# RH039_2.net
KiCad netlist of a schematic drawn in EAGLE
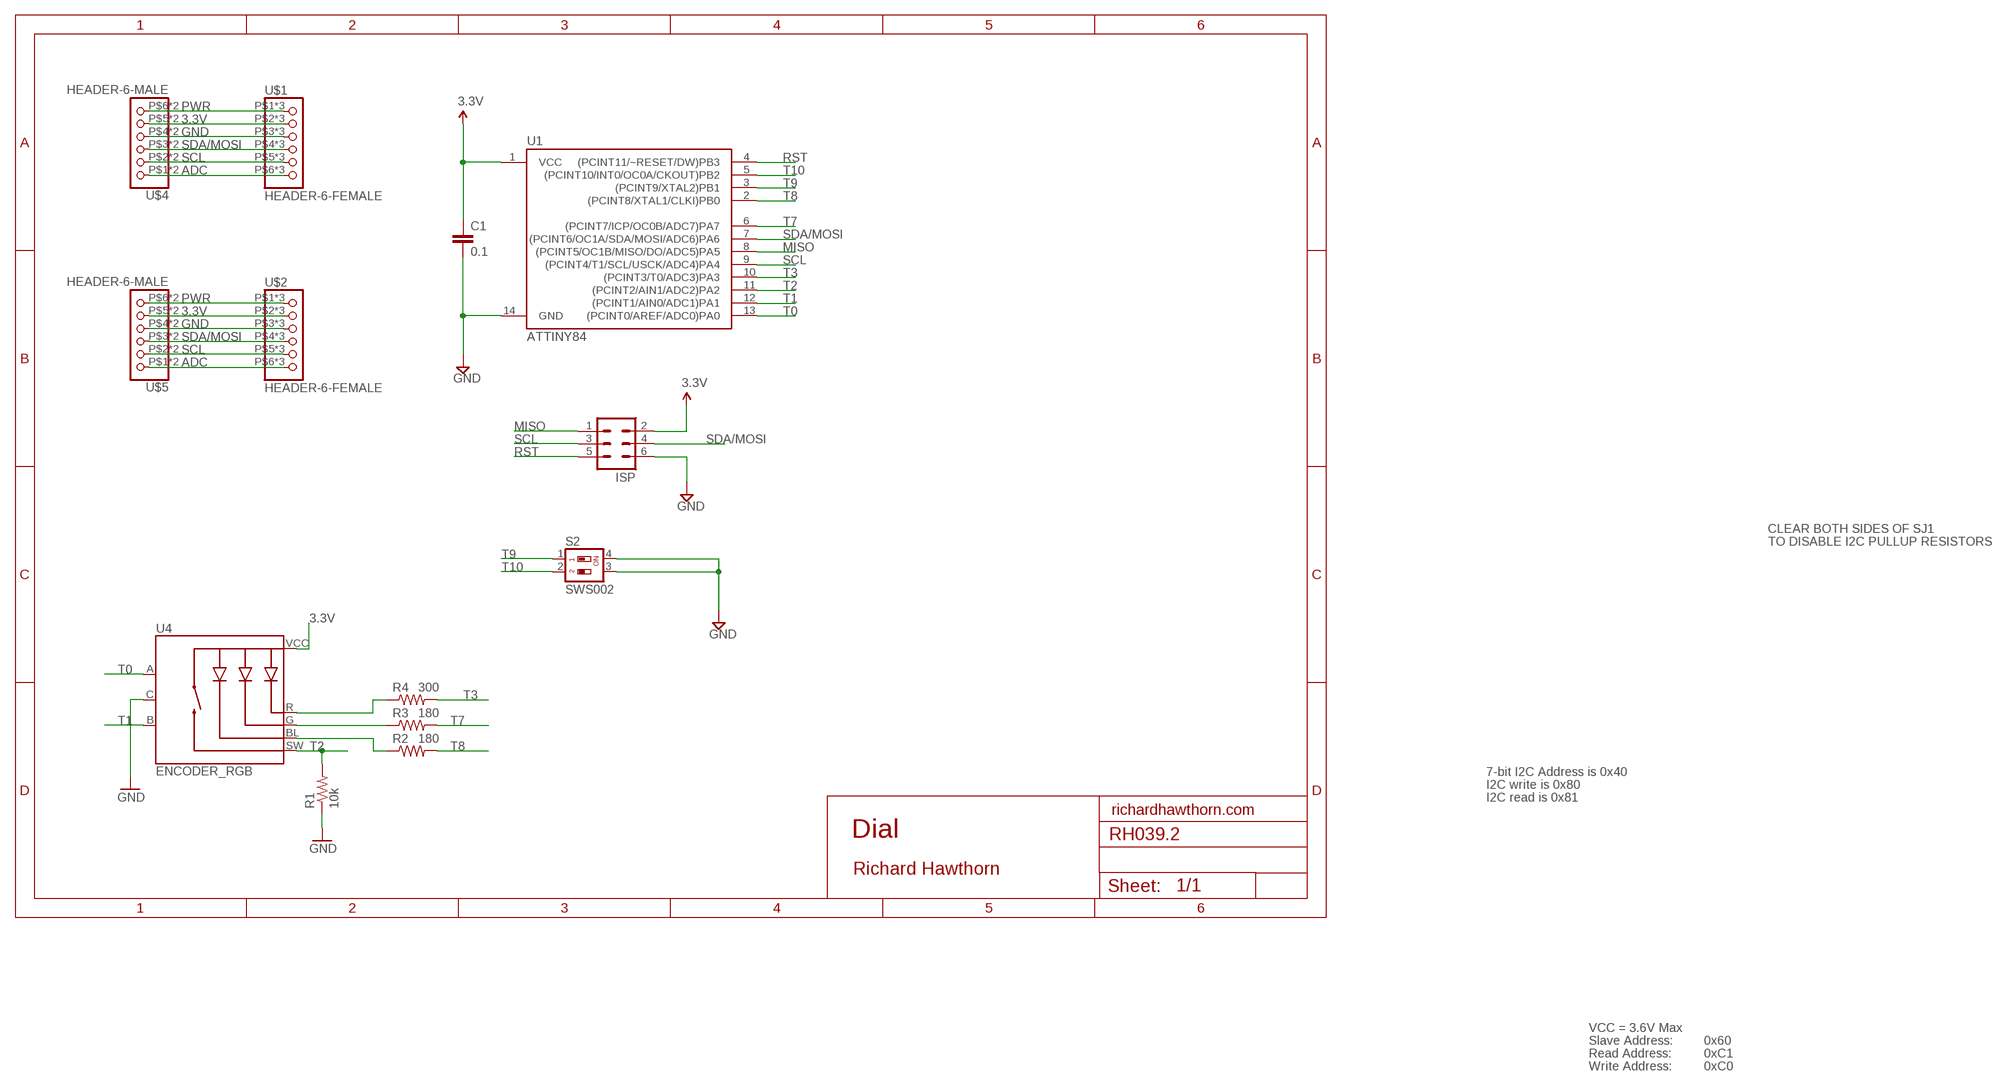
[diagram p0: schematic, sheet 1]

(export (version "E")
  (design (tool "Eeschema 10.0.6"))
  (components
    (comp (ref "C1")
      (value "0.1")
      (footprint "eagle-import:0603-CAP")
      (libsource (lib "eagle-import") (part "CAP0603-CAP"))
    )
    (comp (ref "ISP")
      (value "MA03-2")
      (footprint "eagle-import:MA03-2")
      (libsource (lib "eagle-import") (part "MA03-2"))
    )
    (comp (ref "R1")
      (value "10k")
      (footprint "eagle-import:0402-RES")
      (libsource (lib "eagle-import") (part "RESISTOR0402-RES"))
    )
    (comp (ref "R2")
      (value "180")
      (footprint "eagle-import:0402-RES")
      (libsource (lib "eagle-import") (part "RESISTOR0402-RES"))
    )
    (comp (ref "R3")
      (value "180")
      (footprint "eagle-import:0402-RES")
      (libsource (lib "eagle-import") (part "RESISTOR0402-RES"))
    )
    (comp (ref "R4")
      (value "300")
      (footprint "eagle-import:0402-RES")
      (libsource (lib "eagle-import") (part "RESISTOR0402-RES"))
    )
    (comp (ref "S2")
      (value "SWS002")
      (footprint "eagle-import:SMS-002")
      (libsource (lib "eagle-import") (part "SWS002"))
    )
    (comp (ref "U$1")
      (value "HEADER-6-FEMALE")
      (footprint "eagle-import:2MMHEADER6")
      (libsource (lib "eagle-import") (part "HEADER-6-FEMALE"))
    )
    (comp (ref "U$2")
      (value "HEADER-6-FEMALE")
      (footprint "eagle-import:2MMHEADER6")
      (libsource (lib "eagle-import") (part "HEADER-6-FEMALE"))
    )
    (comp (ref "U$4")
      (value "HEADER-6-MALE")
      (footprint "eagle-import:2MMHEADERPIN6")
      (libsource (lib "eagle-import") (part "HEADER-6-MALE"))
    )
    (comp (ref "U$5")
      (value "HEADER-6-MALE")
      (footprint "eagle-import:2MMHEADERPIN6")
      (libsource (lib "eagle-import") (part "HEADER-6-MALE"))
    )
    (comp (ref "U1")
      (value "ATTINY84")
      (footprint "eagle-import:SO14")
      (libsource (lib "eagle-import") (part "ATTINY84"))
    )
    (comp (ref "U4")
      (value "ENCODER_RGB")
      (footprint "eagle-import:ENCODER_LED_RGB")
      (libsource (lib "eagle-import") (part "ENCODER_RGB"))
    )
  )
  (nets
    (net (code "1") (name "/ADC") (class "Default")
      (node (ref "U$1") (pin "P$14") (pinfunction "6_P$14") (pintype "passive"))
      (node (ref "U$1") (pin "P$22") (pinfunction "6_P$22") (pintype "passive"))
      (node (ref "U$1") (pin "P$6") (pinfunction "6_P$6") (pintype "passive"))
      (node (ref "U$2") (pin "P$14") (pinfunction "6_P$14") (pintype "passive"))
      (node (ref "U$2") (pin "P$22") (pinfunction "6_P$22") (pintype "passive"))
      (node (ref "U$2") (pin "P$6") (pinfunction "6_P$6") (pintype "passive"))
      (node (ref "U$4") (pin "P$1") (pinfunction "1_P$1") (pintype "passive"))
      (node (ref "U$4") (pin "P$9") (pinfunction "1_P$9") (pintype "passive"))
      (node (ref "U$5") (pin "P$1") (pinfunction "1_P$1") (pintype "passive"))
      (node (ref "U$5") (pin "P$9") (pinfunction "1_P$9") (pintype "passive"))
    )
    (net (code "2") (name "/MISO") (class "Default")
      (node (ref "ISP") (pin "1") (pinfunction "1_1") (pintype "passive"))
      (node (ref "U1") (pin "8") (pinfunction "(PCINT5/OC1B/MISO/DO/ADC5)PA5_8") (pintype "bidirectional"))
    )
    (net (code "3") (name "/PWR") (class "Default")
      (node (ref "U$1") (pin "P$1") (pinfunction "1_P$1") (pintype "passive"))
      (node (ref "U$1") (pin "P$17") (pinfunction "1_P$17") (pintype "passive"))
      (node (ref "U$1") (pin "P$9") (pinfunction "1_P$9") (pintype "passive"))
      (node (ref "U$2") (pin "P$1") (pinfunction "1_P$1") (pintype "passive"))
      (node (ref "U$2") (pin "P$17") (pinfunction "1_P$17") (pintype "passive"))
      (node (ref "U$2") (pin "P$9") (pinfunction "1_P$9") (pintype "passive"))
      (node (ref "U$4") (pin "P$14") (pinfunction "6_P$14") (pintype "passive"))
      (node (ref "U$4") (pin "P$6") (pinfunction "6_P$6") (pintype "passive"))
      (node (ref "U$5") (pin "P$14") (pinfunction "6_P$14") (pintype "passive"))
      (node (ref "U$5") (pin "P$6") (pinfunction "6_P$6") (pintype "passive"))
    )
    (net (code "4") (name "/RST") (class "Default")
      (node (ref "ISP") (pin "5") (pinfunction "5_5") (pintype "passive"))
      (node (ref "U1") (pin "4") (pinfunction "(PCINT11/~{RESET/DW})PB3_4") (pintype "bidirectional"))
    )
    (net (code "5") (name "/SCL") (class "Default")
      (node (ref "ISP") (pin "3") (pinfunction "3_3") (pintype "passive"))
      (node (ref "U$1") (pin "P$13") (pinfunction "5_P$13") (pintype "passive"))
      (node (ref "U$1") (pin "P$21") (pinfunction "5_P$21") (pintype "passive"))
      (node (ref "U$1") (pin "P$5") (pinfunction "5_P$5") (pintype "passive"))
      (node (ref "U$2") (pin "P$13") (pinfunction "5_P$13") (pintype "passive"))
      (node (ref "U$2") (pin "P$21") (pinfunction "5_P$21") (pintype "passive"))
      (node (ref "U$2") (pin "P$5") (pinfunction "5_P$5") (pintype "passive"))
      (node (ref "U$4") (pin "P$10") (pinfunction "2_P$10") (pintype "passive"))
      (node (ref "U$4") (pin "P$2") (pinfunction "2_P$2") (pintype "passive"))
      (node (ref "U$5") (pin "P$10") (pinfunction "2_P$10") (pintype "passive"))
      (node (ref "U$5") (pin "P$2") (pinfunction "2_P$2") (pintype "passive"))
      (node (ref "U1") (pin "9") (pinfunction "(PCINT4/T1/SCL/USCK/ADC4)PA4_9") (pintype "bidirectional"))
    )
    (net (code "6") (name "/SDA{slash}MOSI") (class "Default")
      (node (ref "ISP") (pin "4") (pinfunction "4_4") (pintype "passive"))
      (node (ref "U$1") (pin "P$12") (pinfunction "4_P$12") (pintype "passive"))
      (node (ref "U$1") (pin "P$20") (pinfunction "4_P$20") (pintype "passive"))
      (node (ref "U$1") (pin "P$4") (pinfunction "4_P$4") (pintype "passive"))
      (node (ref "U$2") (pin "P$12") (pinfunction "4_P$12") (pintype "passive"))
      (node (ref "U$2") (pin "P$20") (pinfunction "4_P$20") (pintype "passive"))
      (node (ref "U$2") (pin "P$4") (pinfunction "4_P$4") (pintype "passive"))
      (node (ref "U$4") (pin "P$11") (pinfunction "3_P$11") (pintype "passive"))
      (node (ref "U$4") (pin "P$3") (pinfunction "3_P$3") (pintype "passive"))
      (node (ref "U$5") (pin "P$11") (pinfunction "3_P$11") (pintype "passive"))
      (node (ref "U$5") (pin "P$3") (pinfunction "3_P$3") (pintype "passive"))
      (node (ref "U1") (pin "7") (pinfunction "(PCINT6/OC1A/SDA/MOSI/ADC6)PA6_7") (pintype "bidirectional"))
    )
    (net (code "7") (name "/T0") (class "Default")
      (node (ref "U1") (pin "13") (pinfunction "(PCINT0/AREF/ADC0)PA0_13") (pintype "bidirectional"))
      (node (ref "U4") (pin "A") (pinfunction "A_A") (pintype "bidirectional"))
    )
    (net (code "8") (name "/T1") (class "Default")
      (node (ref "U1") (pin "12") (pinfunction "(PCINT1/AIN0/ADC1)PA1_12") (pintype "bidirectional"))
      (node (ref "U4") (pin "B") (pinfunction "B_B") (pintype "bidirectional"))
    )
    (net (code "9") (name "/T2") (class "Default")
      (node (ref "R1") (pin "2") (pinfunction "2_2") (pintype "passive"))
      (node (ref "U1") (pin "11") (pinfunction "(PCINT2/AIN1/ADC2)PA2_11") (pintype "bidirectional"))
      (node (ref "U4") (pin "SW") (pinfunction "SW_SW") (pintype "passive"))
    )
    (net (code "10") (name "/T3") (class "Default")
      (node (ref "R4") (pin "2") (pinfunction "2_2") (pintype "passive"))
      (node (ref "U1") (pin "10") (pinfunction "(PCINT3/T0/ADC3)PA3_10") (pintype "bidirectional"))
    )
    (net (code "11") (name "/T7") (class "Default")
      (node (ref "R3") (pin "2") (pinfunction "2_2") (pintype "passive"))
      (node (ref "U1") (pin "6") (pinfunction "(PCINT7/ICP/OC0B/ADC7)PA7_6") (pintype "bidirectional"))
    )
    (net (code "12") (name "/T8") (class "Default")
      (node (ref "R2") (pin "2") (pinfunction "2_2") (pintype "passive"))
      (node (ref "U1") (pin "2") (pinfunction "(PCINT8/XTAL1/CLKI)PB0_2") (pintype "bidirectional"))
    )
    (net (code "13") (name "/T9") (class "Default")
      (node (ref "S2") (pin "1") (pinfunction "1_1") (pintype "passive"))
      (node (ref "U1") (pin "3") (pinfunction "(PCINT9/XTAL2)PB1_3") (pintype "bidirectional"))
    )
    (net (code "14") (name "/T10") (class "Default")
      (node (ref "S2") (pin "2") (pinfunction "2_2") (pintype "passive"))
      (node (ref "U1") (pin "5") (pinfunction "(PCINT10/INT0/OC0A/CKOUT)PB2_5") (pintype "bidirectional"))
    )
    (net (code "15") (name "3.3V") (class "Default")
      (node (ref "C1") (pin "1") (pinfunction "1_1") (pintype "passive"))
      (node (ref "ISP") (pin "2") (pinfunction "2_2") (pintype "passive"))
      (node (ref "U$1") (pin "P$10") (pinfunction "2_P$10") (pintype "passive"))
      (node (ref "U$1") (pin "P$18") (pinfunction "2_P$18") (pintype "passive"))
      (node (ref "U$1") (pin "P$2") (pinfunction "2_P$2") (pintype "passive"))
      (node (ref "U$2") (pin "P$10") (pinfunction "2_P$10") (pintype "passive"))
      (node (ref "U$2") (pin "P$18") (pinfunction "2_P$18") (pintype "passive"))
      (node (ref "U$2") (pin "P$2") (pinfunction "2_P$2") (pintype "passive"))
      (node (ref "U$4") (pin "P$13") (pinfunction "5_P$13") (pintype "passive"))
      (node (ref "U$4") (pin "P$5") (pinfunction "5_P$5") (pintype "passive"))
      (node (ref "U$5") (pin "P$13") (pinfunction "5_P$13") (pintype "passive"))
      (node (ref "U$5") (pin "P$5") (pinfunction "5_P$5") (pintype "passive"))
      (node (ref "U1") (pin "1") (pinfunction "VCC_1") (pintype "bidirectional"))
      (node (ref "U4") (pin "VCC") (pinfunction "VCC_VCC") (pintype "passive"))
    )
    (net (code "16") (name "GND") (class "Default")
      (node (ref "C1") (pin "2") (pinfunction "2_2") (pintype "passive"))
      (node (ref "ISP") (pin "6") (pinfunction "6_6") (pintype "passive"))
      (node (ref "R1") (pin "1") (pinfunction "1_1") (pintype "passive"))
      (node (ref "S2") (pin "3") (pinfunction "3_3") (pintype "passive"))
      (node (ref "S2") (pin "4") (pinfunction "4_4") (pintype "passive"))
      (node (ref "U$1") (pin "P$11") (pinfunction "3_P$11") (pintype "passive"))
      (node (ref "U$1") (pin "P$19") (pinfunction "3_P$19") (pintype "passive"))
      (node (ref "U$1") (pin "P$3") (pinfunction "3_P$3") (pintype "passive"))
      (node (ref "U$2") (pin "P$11") (pinfunction "3_P$11") (pintype "passive"))
      (node (ref "U$2") (pin "P$19") (pinfunction "3_P$19") (pintype "passive"))
      (node (ref "U$2") (pin "P$3") (pinfunction "3_P$3") (pintype "passive"))
      (node (ref "U$4") (pin "P$12") (pinfunction "4_P$12") (pintype "passive"))
      (node (ref "U$4") (pin "P$4") (pinfunction "4_P$4") (pintype "passive"))
      (node (ref "U$5") (pin "P$12") (pinfunction "4_P$12") (pintype "passive"))
      (node (ref "U$5") (pin "P$4") (pinfunction "4_P$4") (pintype "passive"))
      (node (ref "U1") (pin "14") (pinfunction "GND_14") (pintype "bidirectional"))
      (node (ref "U4") (pin "C") (pinfunction "C_C") (pintype "bidirectional"))
    )
    (net (code "17") (name "Net-(R2-Pad1)") (class "Default")
      (node (ref "R2") (pin "1") (pinfunction "1_1") (pintype "passive"))
      (node (ref "U4") (pin "BL") (pinfunction "BL_BL") (pintype "passive"))
    )
    (net (code "18") (name "Net-(R3-Pad1)") (class "Default")
      (node (ref "R3") (pin "1") (pinfunction "1_1") (pintype "passive"))
      (node (ref "U4") (pin "G") (pinfunction "G_G") (pintype "passive"))
    )
    (net (code "19") (name "Net-(R4-Pad1)") (class "Default")
      (node (ref "R4") (pin "1") (pinfunction "1_1") (pintype "passive"))
      (node (ref "U4") (pin "R") (pinfunction "R_R") (pintype "passive"))
    )
  )
)
